# ife18_TS_AIL_Buck.net
KiCad netlist of a schematic drawn in Altium Designer
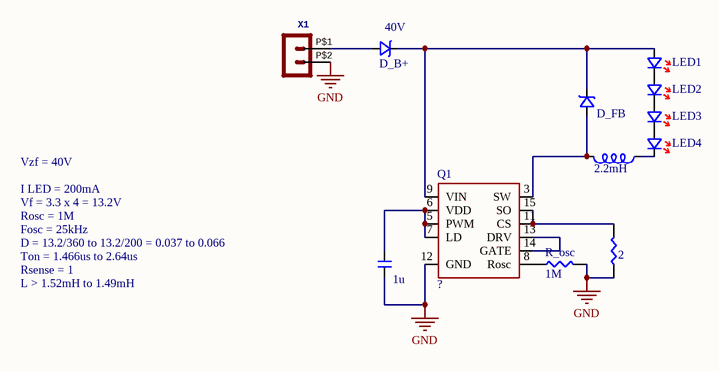
[diagram p0: ife18_TS_AIL_Buck.SchDoc]

(export (version "E")
  (design (tool "Eeschema 10.0.6"))
  (components
    (comp (ref "C_VDD")
      (value "1u")
      (footprint "CAP-0603")
      (libsource (lib "ife19_Elec_Library") (part "CAP-0603"))
    )
    (comp (ref "D_B+")
      (value "40V")
      (footprint "SMB")
      (libsource (lib "ife19_Elec_Library") (part "DIODE-SMB"))
    )
    (comp (ref "D_FB")
      (value "?")
      (footprint "SMB")
      (libsource (lib "ife19_Elec_Library") (part "DIODE-SMB"))
    )
    (comp (ref "IND")
      (value "2.2mH")
      (footprint "IND-8080")
      (libsource (lib "ife19_Elec_Library") (part "IND-8080"))
    )
    (comp (ref "LED1")
      (value "LED XQA Red")
      (footprint "LED_XQARED")
      (libsource (lib "ife19_Elec_Library") (part "LED_XQARED"))
    )
    (comp (ref "LED2")
      (value "LED XQA Red")
      (footprint "LED_XQARED")
      (libsource (lib "ife19_Elec_Library") (part "LED_XQARED"))
    )
    (comp (ref "LED3")
      (value "LED XQA Red")
      (footprint "LED_XQARED")
      (libsource (lib "ife19_Elec_Library") (part "LED_XQARED"))
    )
    (comp (ref "LED4")
      (value "LED XQA Red")
      (footprint "LED_XQARED")
      (libsource (lib "ife19_Elec_Library") (part "LED_XQARED"))
    )
    (comp (ref "Q1")
      (value "?")
      (footprint "SO-16")
      (libsource (lib "ife19_Elec_Library") (part "IC-SO16_AL9901_1"))
    )
    (comp (ref "R_osc")
      (value "1M")
      (footprint "RES-0603")
      (libsource (lib "ife19_Elec_Library") (part "RES-0603"))
    )
    (comp (ref "R_sense")
      (value "2")
      (footprint "RES-0603")
      (libsource (lib "ife19_Elec_Library") (part "RES-0603"))
    )
    (comp (ref "X1")
      (value "Molex - Micro-Fit 3.0 Series connector,  3.00mm (0.118\") pitch header, 2 positions.")
      (footprint "43650-0224")
      (libsource (lib "ife19_Elec_Conn_Library") (part "POS2_MF43650-0224"))
    )
  )
  (nets
    (net (code "1") (name "GND") (class "Default")
      (node (ref "C_VDD") (pin "1") (pinfunction "1_1") (pintype "passive"))
      (node (ref "Q1") (pin "12") (pinfunction "GND_12") (pintype "passive"))
      (node (ref "R_osc") (pin "2") (pinfunction "2_2") (pintype "passive"))
      (node (ref "R_sense") (pin "1") (pinfunction "1_1") (pintype "passive"))
      (node (ref "X1") (pin "P$2") (pinfunction "2_P$2") (pintype "passive"))
    )
    (net (code "2") (name "Net-(IND-Pad1)") (class "Default")
      (node (ref "IND") (pin "1") (pinfunction "1_1") (pintype "passive"))
      (node (ref "LED4") (pin "K") (pinfunction "K_K") (pintype "passive"))
    )
    (net (code "3") (name "Net-(LED1-PadK)") (class "Default")
      (node (ref "LED1") (pin "K") (pinfunction "K_K") (pintype "passive"))
      (node (ref "LED2") (pin "A") (pinfunction "A_A") (pintype "passive"))
    )
    (net (code "4") (name "Net-(LED2-PadK)") (class "Default")
      (node (ref "LED2") (pin "K") (pinfunction "K_K") (pintype "passive"))
      (node (ref "LED3") (pin "A") (pinfunction "A_A") (pintype "passive"))
    )
    (net (code "5") (name "Net-(LED3-PadK)") (class "Default")
      (node (ref "LED3") (pin "K") (pinfunction "K_K") (pintype "passive"))
      (node (ref "LED4") (pin "A") (pinfunction "A_A") (pintype "passive"))
    )
    (net (code "6") (name "Net-(Q1-CS)") (class "Default")
      (node (ref "Q1") (pin "11") (pinfunction "CS_11") (pintype "passive"))
      (node (ref "Q1") (pin "15") (pinfunction "SO_15") (pintype "passive"))
      (node (ref "R_sense") (pin "2") (pinfunction "2_2") (pintype "passive"))
    )
    (net (code "7") (name "Net-(Q1-DRV)") (class "Default")
      (node (ref "Q1") (pin "13") (pinfunction "DRV_13") (pintype "passive"))
      (node (ref "Q1") (pin "14") (pinfunction "GATE_14") (pintype "passive"))
    )
    (net (code "8") (name "Net-(Q1-LD)") (class "Default")
      (node (ref "C_VDD") (pin "2") (pinfunction "2_2") (pintype "passive"))
      (node (ref "Q1") (pin "5") (pinfunction "PWM_5") (pintype "passive"))
      (node (ref "Q1") (pin "6") (pinfunction "VDD_6") (pintype "passive"))
      (node (ref "Q1") (pin "7") (pinfunction "LD_7") (pintype "passive"))
    )
    (net (code "9") (name "Net-(Q1-Rosc)") (class "Default")
      (node (ref "Q1") (pin "8") (pinfunction "Rosc_8") (pintype "passive"))
      (node (ref "R_osc") (pin "1") (pinfunction "1_1") (pintype "passive"))
    )
    (net (code "10") (name "Net-(Q1-SW)") (class "Default")
      (node (ref "D_FB") (pin "A") (pinfunction "A_A") (pintype "passive"))
      (node (ref "IND") (pin "2") (pinfunction "2_2") (pintype "passive"))
      (node (ref "Q1") (pin "3") (pinfunction "SW_3") (pintype "passive"))
    )
    (net (code "11") (name "Net-(Q1-VIN)") (class "Default")
      (node (ref "D_B+") (pin "K") (pinfunction "K_K") (pintype "passive"))
      (node (ref "D_FB") (pin "K") (pinfunction "K_K") (pintype "passive"))
      (node (ref "LED1") (pin "A") (pinfunction "A_A") (pintype "passive"))
      (node (ref "Q1") (pin "9") (pinfunction "VIN_9") (pintype "passive"))
    )
    (net (code "12") (name "Net-(X1-1)") (class "Default")
      (node (ref "D_B+") (pin "A") (pinfunction "A_A") (pintype "passive"))
      (node (ref "X1") (pin "P$1") (pinfunction "1_P$1") (pintype "passive"))
    )
  )
)
